# TRV_CC110x_V0_1a.net
KiCad netlist of a schematic drawn in EAGLE
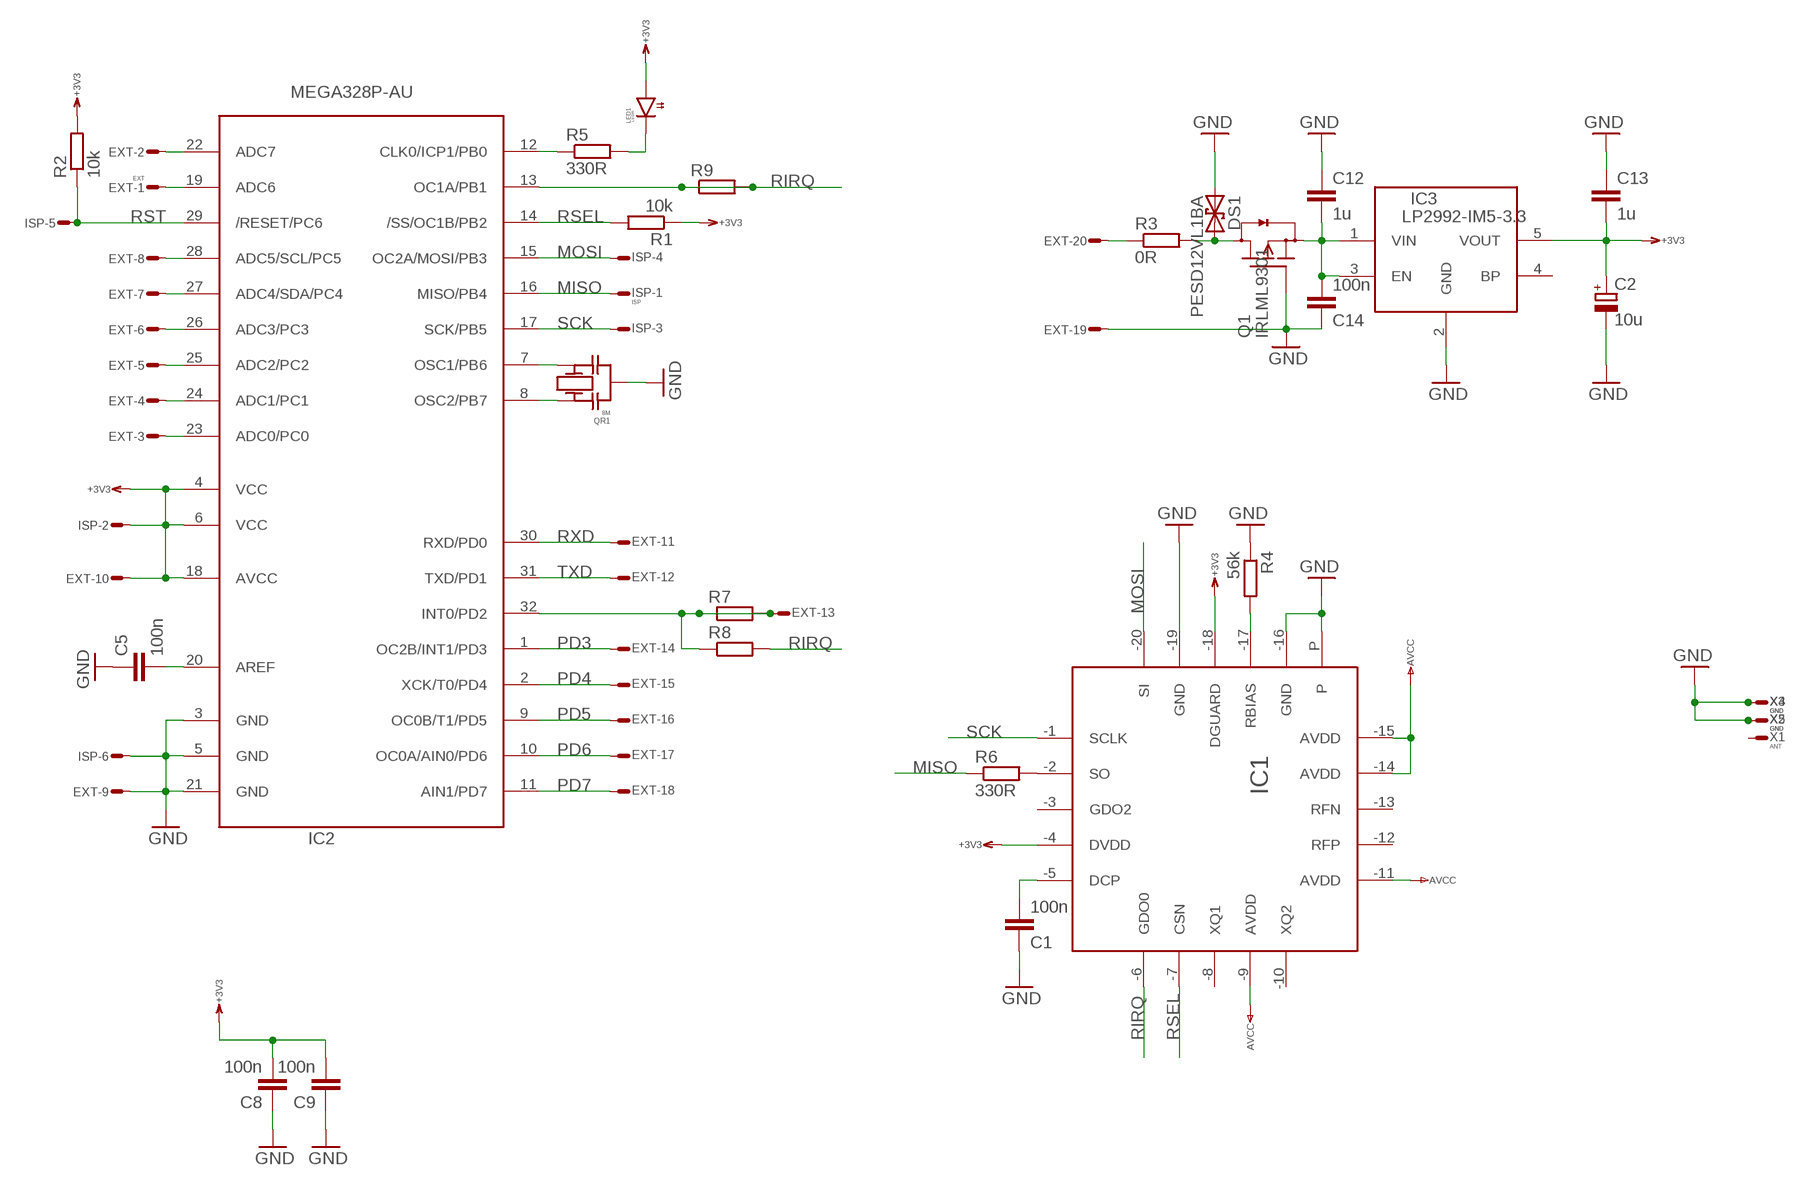
[diagram p0: schematic, sheet 1]

(export (version "E")
  (design (tool "Eeschema 10.0.6"))
  (components
    (comp (ref "C1")
      (value "100n")
      (footprint "eagle-import:0603")
      (libsource (lib "eagle-import") (part "C0603"))
    )
    (comp (ref "C2")
      (value "10u")
      (footprint "eagle-import:SMC_B")
      (libsource (lib "eagle-import") (part "C_POLSMCB"))
    )
    (comp (ref "C5")
      (value "100n")
      (footprint "eagle-import:0603")
      (libsource (lib "eagle-import") (part "C0603"))
    )
    (comp (ref "C8")
      (value "100n")
      (footprint "eagle-import:0603")
      (libsource (lib "eagle-import") (part "C0603"))
    )
    (comp (ref "C9")
      (value "100n")
      (footprint "eagle-import:0603")
      (libsource (lib "eagle-import") (part "C0603"))
    )
    (comp (ref "C12")
      (value "1u")
      (footprint "eagle-import:0603")
      (libsource (lib "eagle-import") (part "C0603"))
    )
    (comp (ref "C13")
      (value "1u")
      (footprint "eagle-import:0603")
      (libsource (lib "eagle-import") (part "C0603"))
    )
    (comp (ref "C14")
      (value "100n")
      (footprint "eagle-import:0603")
      (libsource (lib "eagle-import") (part "C0603"))
    )
    (comp (ref "DS1")
      (value "PESD12VL1BA")
      (footprint "eagle-import:SOD323")
      (libsource (lib "eagle-import") (part "TVS-U323"))
    )
    (comp (ref "EXT")
      (value "EXT")
      (footprint "eagle-import:ML20S")
      (libsource (lib "eagle-import") (part "ML20?ES"))
    )
    (comp (ref "IC1")
      (value "CC110L")
      (footprint "eagle-import:VQFN20")
      (libsource (lib "eagle-import") (part "CC110L"))
    )
    (comp (ref "IC2")
      (value "MEGA328P-AU")
      (footprint "eagle-import:TQFP32-08")
      (libsource (lib "eagle-import") (part "MEGA168PA"))
    )
    (comp (ref "IC3")
      (value "LP2992-IM5-3.3")
      (footprint "eagle-import:SOT23-5")
      (libsource (lib "eagle-import") (part "LDO"))
    )
    (comp (ref "ISP")
      (value "ISP")
      (footprint "eagle-import:ML6S")
      (libsource (lib "eagle-import") (part "ML6ES"))
    )
    (comp (ref "LED1")
      (value "LEDR")
      (footprint "eagle-import:0805")
      (libsource (lib "eagle-import") (part "LED0805"))
    )
    (comp (ref "Q1")
      (value "IRLML9301")
      (footprint "eagle-import:SOT23")
      (libsource (lib "eagle-import") (part "FET-PDSOT23"))
    )
    (comp (ref "QR1")
      (value "8M")
      (footprint "eagle-import:CR")
      (libsource (lib "eagle-import") (part "QRCR"))
    )
    (comp (ref "R1")
      (value "10k")
      (footprint "eagle-import:0603")
      (libsource (lib "eagle-import") (part "R0603"))
    )
    (comp (ref "R2")
      (value "10k")
      (footprint "eagle-import:0603")
      (libsource (lib "eagle-import") (part "R0603"))
    )
    (comp (ref "R3")
      (value "0R")
      (footprint "eagle-import:0603")
      (libsource (lib "eagle-import") (part "R0603"))
    )
    (comp (ref "R4")
      (value "56k")
      (footprint "eagle-import:0603")
      (libsource (lib "eagle-import") (part "R0603"))
    )
    (comp (ref "R5")
      (value "330R")
      (footprint "eagle-import:0603")
      (libsource (lib "eagle-import") (part "R0603"))
    )
    (comp (ref "R6")
      (value "330R")
      (footprint "eagle-import:0603")
      (libsource (lib "eagle-import") (part "R0603"))
    )
    (comp (ref "R7")
      (value "R0603")
      (footprint "eagle-import:0603")
      (libsource (lib "eagle-import") (part "R0603"))
    )
    (comp (ref "R8")
      (value "R0603")
      (footprint "eagle-import:0603")
      (libsource (lib "eagle-import") (part "R0603"))
    )
    (comp (ref "R9")
      (value "R0603")
      (footprint "eagle-import:0603")
      (libsource (lib "eagle-import") (part "R0603"))
    )
    (comp (ref "X1")
      (value "ANT")
      (footprint "eagle-import:S2.54_1.27")
      (libsource (lib "eagle-import") (part "WIREPADS2.54/1.27"))
    )
    (comp (ref "X2")
      (value "GND")
      (footprint "eagle-import:S2.54_1.27")
      (libsource (lib "eagle-import") (part "WIREPADS2.54/1.27"))
    )
    (comp (ref "X3")
      (value "GND")
      (footprint "eagle-import:S2.54_1.27")
      (libsource (lib "eagle-import") (part "WIREPADS2.54/1.27"))
    )
    (comp (ref "X4")
      (value "GND")
      (footprint "eagle-import:S2.54_1.27")
      (libsource (lib "eagle-import") (part "WIREPADS2.54/1.27"))
    )
    (comp (ref "X5")
      (value "GND")
      (footprint "eagle-import:S2.54_1.27")
      (libsource (lib "eagle-import") (part "WIREPADS2.54/1.27"))
    )
  )
  (nets
    (net (code "1") (name "+3V3") (class "Default")
      (node (ref "C13") (pin "2") (pinfunction "2_2") (pintype "passive"))
      (node (ref "C2") (pin "+") (pinfunction "+_+") (pintype "passive"))
      (node (ref "C8") (pin "2") (pinfunction "2_2") (pintype "passive"))
      (node (ref "C9") (pin "2") (pinfunction "2_2") (pintype "passive"))
      (node (ref "EXT") (pin "10") (pinfunction "S_10") (pintype "passive"))
      (node (ref "IC1") (pin "-18") (pinfunction "DGUARD_-18") (pintype "bidirectional"))
      (node (ref "IC1") (pin "-4") (pinfunction "DVDD_-4") (pintype "bidirectional"))
      (node (ref "IC2") (pin "18") (pinfunction "AVCC_18") (pintype "bidirectional"))
      (node (ref "IC2") (pin "4") (pinfunction "VCC_4") (pintype "bidirectional"))
      (node (ref "IC2") (pin "6") (pinfunction "VCC_6") (pintype "bidirectional"))
      (node (ref "IC3") (pin "5") (pinfunction "VOUT_5") (pintype "bidirectional"))
      (node (ref "ISP") (pin "2") (pinfunction "S_2") (pintype "passive"))
      (node (ref "LED1") (pin "C") (pinfunction "A_C") (pintype "bidirectional"))
      (node (ref "R1") (pin "1") (pinfunction "1_1") (pintype "passive"))
      (node (ref "R2") (pin "2") (pinfunction "2_2") (pintype "passive"))
    )
    (net (code "2") (name "/MISO") (class "Default")
      (node (ref "IC2") (pin "16") (pinfunction "MISO/PB4_16") (pintype "bidirectional"))
      (node (ref "ISP") (pin "1") (pinfunction "S_1") (pintype "passive"))
      (node (ref "R6") (pin "1") (pinfunction "1_1") (pintype "passive"))
    )
    (net (code "3") (name "/MOSI") (class "Default")
      (node (ref "IC1") (pin "-20") (pinfunction "SI_-20") (pintype "input"))
      (node (ref "IC2") (pin "15") (pinfunction "OC2A/MOSI/PB3_15") (pintype "bidirectional"))
      (node (ref "ISP") (pin "4") (pinfunction "S_4") (pintype "passive"))
    )
    (net (code "4") (name "/PD3") (class "Default")
      (node (ref "EXT") (pin "14") (pinfunction "S_14") (pintype "passive"))
      (node (ref "IC2") (pin "1") (pinfunction "OC2B/INT1/PD3_1") (pintype "bidirectional"))
    )
    (net (code "5") (name "/PD4") (class "Default")
      (node (ref "EXT") (pin "15") (pinfunction "S_15") (pintype "passive"))
      (node (ref "IC2") (pin "2") (pinfunction "XCK/T0/PD4_2") (pintype "bidirectional"))
    )
    (net (code "6") (name "/PD5") (class "Default")
      (node (ref "EXT") (pin "16") (pinfunction "S_16") (pintype "passive"))
      (node (ref "IC2") (pin "9") (pinfunction "OC0B/T1/PD5_9") (pintype "bidirectional"))
    )
    (net (code "7") (name "/PD6") (class "Default")
      (node (ref "EXT") (pin "17") (pinfunction "S_17") (pintype "passive"))
      (node (ref "IC2") (pin "10") (pinfunction "OC0A/AIN0/PD6_10") (pintype "bidirectional"))
    )
    (net (code "8") (name "/PD7") (class "Default")
      (node (ref "EXT") (pin "18") (pinfunction "S_18") (pintype "passive"))
      (node (ref "IC2") (pin "11") (pinfunction "AIN1/PD7_11") (pintype "bidirectional"))
    )
    (net (code "9") (name "/RIRQ") (class "Default")
      (node (ref "IC1") (pin "-6") (pinfunction "GDO0_-6") (pintype "bidirectional"))
      (node (ref "IC2") (pin "13") (pinfunction "OC1A/PB1_13") (pintype "bidirectional"))
      (node (ref "R8") (pin "2") (pinfunction "2_2") (pintype "passive"))
      (node (ref "R9") (pin "1") (pinfunction "1_1") (pintype "passive"))
      (node (ref "R9") (pin "2") (pinfunction "2_2") (pintype "passive"))
    )
    (net (code "10") (name "/RSEL") (class "Default")
      (node (ref "IC1") (pin "-7") (pinfunction "CSN_-7") (pintype "input"))
      (node (ref "IC2") (pin "14") (pinfunction "/SS/OC1B/PB2_14") (pintype "bidirectional"))
      (node (ref "R1") (pin "2") (pinfunction "2_2") (pintype "passive"))
    )
    (net (code "11") (name "/RST") (class "Default")
      (node (ref "IC2") (pin "29") (pinfunction "/RESET/PC6_29") (pintype "bidirectional"))
      (node (ref "ISP") (pin "5") (pinfunction "S_5") (pintype "passive"))
      (node (ref "R2") (pin "1") (pinfunction "1_1") (pintype "passive"))
    )
    (net (code "12") (name "/RXD") (class "Default")
      (node (ref "EXT") (pin "11") (pinfunction "S_11") (pintype "passive"))
      (node (ref "IC2") (pin "30") (pinfunction "RXD/PD0_30") (pintype "bidirectional"))
    )
    (net (code "13") (name "/SCK") (class "Default")
      (node (ref "IC1") (pin "-1") (pinfunction "SCLK_-1") (pintype "input"))
      (node (ref "IC2") (pin "17") (pinfunction "SCK/PB5_17") (pintype "bidirectional"))
      (node (ref "ISP") (pin "3") (pinfunction "S_3") (pintype "passive"))
    )
    (net (code "14") (name "/TXD") (class "Default")
      (node (ref "EXT") (pin "12") (pinfunction "S_12") (pintype "passive"))
      (node (ref "IC2") (pin "31") (pinfunction "TXD/PD1_31") (pintype "bidirectional"))
    )
    (net (code "15") (name "AVCC") (class "Default")
      (node (ref "IC1") (pin "-11") (pinfunction "AVDD_-11") (pintype "bidirectional"))
      (node (ref "IC1") (pin "-14") (pinfunction "AVDD_-14") (pintype "bidirectional"))
      (node (ref "IC1") (pin "-15") (pinfunction "AVDD_-15") (pintype "bidirectional"))
      (node (ref "IC1") (pin "-9") (pinfunction "AVDD_-9") (pintype "bidirectional"))
    )
    (net (code "16") (name "GND") (class "Default")
      (node (ref "C1") (pin "1") (pinfunction "1_1") (pintype "passive"))
      (node (ref "C12") (pin "1") (pinfunction "1_1") (pintype "passive"))
      (node (ref "C13") (pin "1") (pinfunction "1_1") (pintype "passive"))
      (node (ref "C14") (pin "1") (pinfunction "1_1") (pintype "passive"))
      (node (ref "C2") (pin "-") (pinfunction "-_-") (pintype "passive"))
      (node (ref "C5") (pin "1") (pinfunction "1_1") (pintype "passive"))
      (node (ref "C8") (pin "1") (pinfunction "1_1") (pintype "passive"))
      (node (ref "C9") (pin "1") (pinfunction "1_1") (pintype "passive"))
      (node (ref "DS1") (pin "A") (pinfunction "1_A") (pintype "passive"))
      (node (ref "EXT") (pin "19") (pinfunction "S_19") (pintype "passive"))
      (node (ref "EXT") (pin "9") (pinfunction "S_9") (pintype "passive"))
      (node (ref "IC1") (pin "-16") (pinfunction "GND_-16") (pintype "bidirectional"))
      (node (ref "IC1") (pin "-19") (pinfunction "GND_-19") (pintype "bidirectional"))
      (node (ref "IC1") (pin "P") (pinfunction "P_P") (pintype "bidirectional"))
      (node (ref "IC2") (pin "21") (pinfunction "GND_21") (pintype "bidirectional"))
      (node (ref "IC2") (pin "3") (pinfunction "GND_3") (pintype "bidirectional"))
      (node (ref "IC2") (pin "5") (pinfunction "GND_5") (pintype "bidirectional"))
      (node (ref "IC3") (pin "2") (pinfunction "GND_2") (pintype "bidirectional"))
      (node (ref "ISP") (pin "6") (pinfunction "S_6") (pintype "passive"))
      (node (ref "Q1") (pin "1") (pinfunction "G_1") (pintype "passive"))
      (node (ref "QR1") (pin "M") (pinfunction "M_M") (pintype "passive"))
      (node (ref "R4") (pin "1") (pinfunction "1_1") (pintype "passive"))
      (node (ref "X2") (pin "1") (pinfunction "S_1") (pintype "passive"))
      (node (ref "X3") (pin "1") (pinfunction "S_1") (pintype "passive"))
      (node (ref "X4") (pin "1") (pinfunction "S_1") (pintype "passive"))
      (node (ref "X5") (pin "1") (pinfunction "S_1") (pintype "passive"))
    )
    (net (code "17") (name "Net-(DS1-2)") (class "Default")
      (node (ref "DS1") (pin "C") (pinfunction "2_C") (pintype "passive"))
      (node (ref "Q1") (pin "3") (pinfunction "D_3") (pintype "passive"))
      (node (ref "R3") (pin "2") (pinfunction "2_2") (pintype "passive"))
    )
    (net (code "18") (name "Net-(EXTA-S)") (class "Default")
      (node (ref "EXT") (pin "1") (pinfunction "S_1") (pintype "passive"))
      (node (ref "IC2") (pin "19") (pinfunction "ADC6_19") (pintype "bidirectional"))
    )
    (net (code "19") (name "Net-(EXTE-S)") (class "Default")
      (node (ref "EXT") (pin "13") (pinfunction "S_13") (pintype "passive"))
      (node (ref "IC2") (pin "32") (pinfunction "INT0/PD2_32") (pintype "bidirectional"))
      (node (ref "R7") (pin "1") (pinfunction "1_1") (pintype "passive"))
      (node (ref "R7") (pin "2") (pinfunction "2_2") (pintype "passive"))
      (node (ref "R8") (pin "1") (pinfunction "1_1") (pintype "passive"))
    )
    (net (code "20") (name "Net-(EXTL-S)") (class "Default")
      (node (ref "EXT") (pin "2") (pinfunction "S_2") (pintype "passive"))
      (node (ref "IC2") (pin "22") (pinfunction "ADC7_22") (pintype "bidirectional"))
    )
    (net (code "21") (name "Net-(EXTM-S)") (class "Default")
      (node (ref "EXT") (pin "20") (pinfunction "S_20") (pintype "passive"))
      (node (ref "R3") (pin "1") (pinfunction "1_1") (pintype "passive"))
    )
    (net (code "22") (name "Net-(EXTN-S)") (class "Default")
      (node (ref "EXT") (pin "3") (pinfunction "S_3") (pintype "passive"))
      (node (ref "IC2") (pin "23") (pinfunction "ADC0/PC0_23") (pintype "bidirectional"))
    )
    (net (code "23") (name "Net-(EXTO-S)") (class "Default")
      (node (ref "EXT") (pin "4") (pinfunction "S_4") (pintype "passive"))
      (node (ref "IC2") (pin "24") (pinfunction "ADC1/PC1_24") (pintype "bidirectional"))
    )
    (net (code "24") (name "Net-(EXTP-S)") (class "Default")
      (node (ref "EXT") (pin "5") (pinfunction "S_5") (pintype "passive"))
      (node (ref "IC2") (pin "25") (pinfunction "ADC2/PC2_25") (pintype "bidirectional"))
    )
    (net (code "25") (name "Net-(EXTQ-S)") (class "Default")
      (node (ref "EXT") (pin "6") (pinfunction "S_6") (pintype "passive"))
      (node (ref "IC2") (pin "26") (pinfunction "ADC3/PC3_26") (pintype "bidirectional"))
    )
    (net (code "26") (name "Net-(EXTR-S)") (class "Default")
      (node (ref "EXT") (pin "7") (pinfunction "S_7") (pintype "passive"))
      (node (ref "IC2") (pin "27") (pinfunction "ADC4/SDA/PC4_27") (pintype "bidirectional"))
    )
    (net (code "27") (name "Net-(EXTS-S)") (class "Default")
      (node (ref "EXT") (pin "8") (pinfunction "S_8") (pintype "passive"))
      (node (ref "IC2") (pin "28") (pinfunction "ADC5/SCL/PC5_28") (pintype "bidirectional"))
    )
    (net (code "28") (name "Net-(IC1-DCP)") (class "Default")
      (node (ref "C1") (pin "2") (pinfunction "2_2") (pintype "passive"))
      (node (ref "IC1") (pin "-5") (pinfunction "DCP_-5") (pintype "bidirectional"))
    )
    (net (code "29") (name "Net-(IC1-RBIAS)") (class "Default")
      (node (ref "IC1") (pin "-17") (pinfunction "RBIAS_-17") (pintype "bidirectional"))
      (node (ref "R4") (pin "2") (pinfunction "2_2") (pintype "passive"))
    )
    (net (code "30") (name "Net-(IC1-SO)") (class "Default")
      (node (ref "IC1") (pin "-2") (pinfunction "SO_-2") (pintype "output"))
      (node (ref "R6") (pin "2") (pinfunction "2_2") (pintype "passive"))
    )
    (net (code "31") (name "Net-(IC2-AREF)") (class "Default")
      (node (ref "C5") (pin "2") (pinfunction "2_2") (pintype "passive"))
      (node (ref "IC2") (pin "20") (pinfunction "AREF_20") (pintype "bidirectional"))
    )
    (net (code "32") (name "Net-(IC2-CLK0{slash}ICP1{slash}PB0)") (class "Default")
      (node (ref "IC2") (pin "12") (pinfunction "CLK0/ICP1/PB0_12") (pintype "bidirectional"))
      (node (ref "R5") (pin "1") (pinfunction "1_1") (pintype "passive"))
    )
    (net (code "33") (name "Net-(IC2-OSC1{slash}PB6)") (class "Default")
      (node (ref "IC2") (pin "7") (pinfunction "OSC1/PB6_7") (pintype "bidirectional"))
      (node (ref "QR1") (pin "2") (pinfunction "2_2") (pintype "passive"))
    )
    (net (code "34") (name "Net-(IC2-OSC2{slash}PB7)") (class "Default")
      (node (ref "IC2") (pin "8") (pinfunction "OSC2/PB7_8") (pintype "bidirectional"))
      (node (ref "QR1") (pin "1") (pinfunction "1_1") (pintype "passive"))
    )
    (net (code "35") (name "Net-(IC3-EN)") (class "Default")
      (node (ref "C12") (pin "2") (pinfunction "2_2") (pintype "passive"))
      (node (ref "C14") (pin "2") (pinfunction "2_2") (pintype "passive"))
      (node (ref "IC3") (pin "1") (pinfunction "VIN_1") (pintype "bidirectional"))
      (node (ref "IC3") (pin "3") (pinfunction "EN_3") (pintype "bidirectional"))
      (node (ref "Q1") (pin "2") (pinfunction "S_2") (pintype "passive"))
    )
    (net (code "36") (name "Net-(LED1-C)") (class "Default")
      (node (ref "LED1") (pin "A") (pinfunction "C_A") (pintype "bidirectional"))
      (node (ref "R5") (pin "2") (pinfunction "2_2") (pintype "passive"))
    )
    (net (code "37") (name "unconnected-(IC1-GDO2-Pad-3)") (class "Default")
      (node (ref "IC1") (pin "-3") (pinfunction "GDO2_-3") (pintype "output"))
    )
    (net (code "38") (name "unconnected-(IC1-RFN-Pad-13)") (class "Default")
      (node (ref "IC1") (pin "-13") (pinfunction "RFN_-13") (pintype "bidirectional"))
    )
    (net (code "39") (name "unconnected-(IC1-RFP-Pad-12)") (class "Default")
      (node (ref "IC1") (pin "-12") (pinfunction "RFP_-12") (pintype "bidirectional"))
    )
    (net (code "40") (name "unconnected-(IC1-XQ1-Pad-8)") (class "Default")
      (node (ref "IC1") (pin "-8") (pinfunction "XQ1_-8") (pintype "bidirectional"))
    )
    (net (code "41") (name "unconnected-(IC1-XQ2-Pad-10)") (class "Default")
      (node (ref "IC1") (pin "-10") (pinfunction "XQ2_-10") (pintype "bidirectional"))
    )
    (net (code "42") (name "unconnected-(IC3-BP-Pad4)") (class "Default")
      (node (ref "IC3") (pin "4") (pinfunction "BP_4") (pintype "bidirectional"))
    )
    (net (code "43") (name "unconnected-(X1-S-Pad1)") (class "Default")
      (node (ref "X1") (pin "1") (pinfunction "S_1") (pintype "passive"))
    )
  )
)
